# Duckietown_2018C.net
KiCad netlist of a schematic drawn in EAGLE
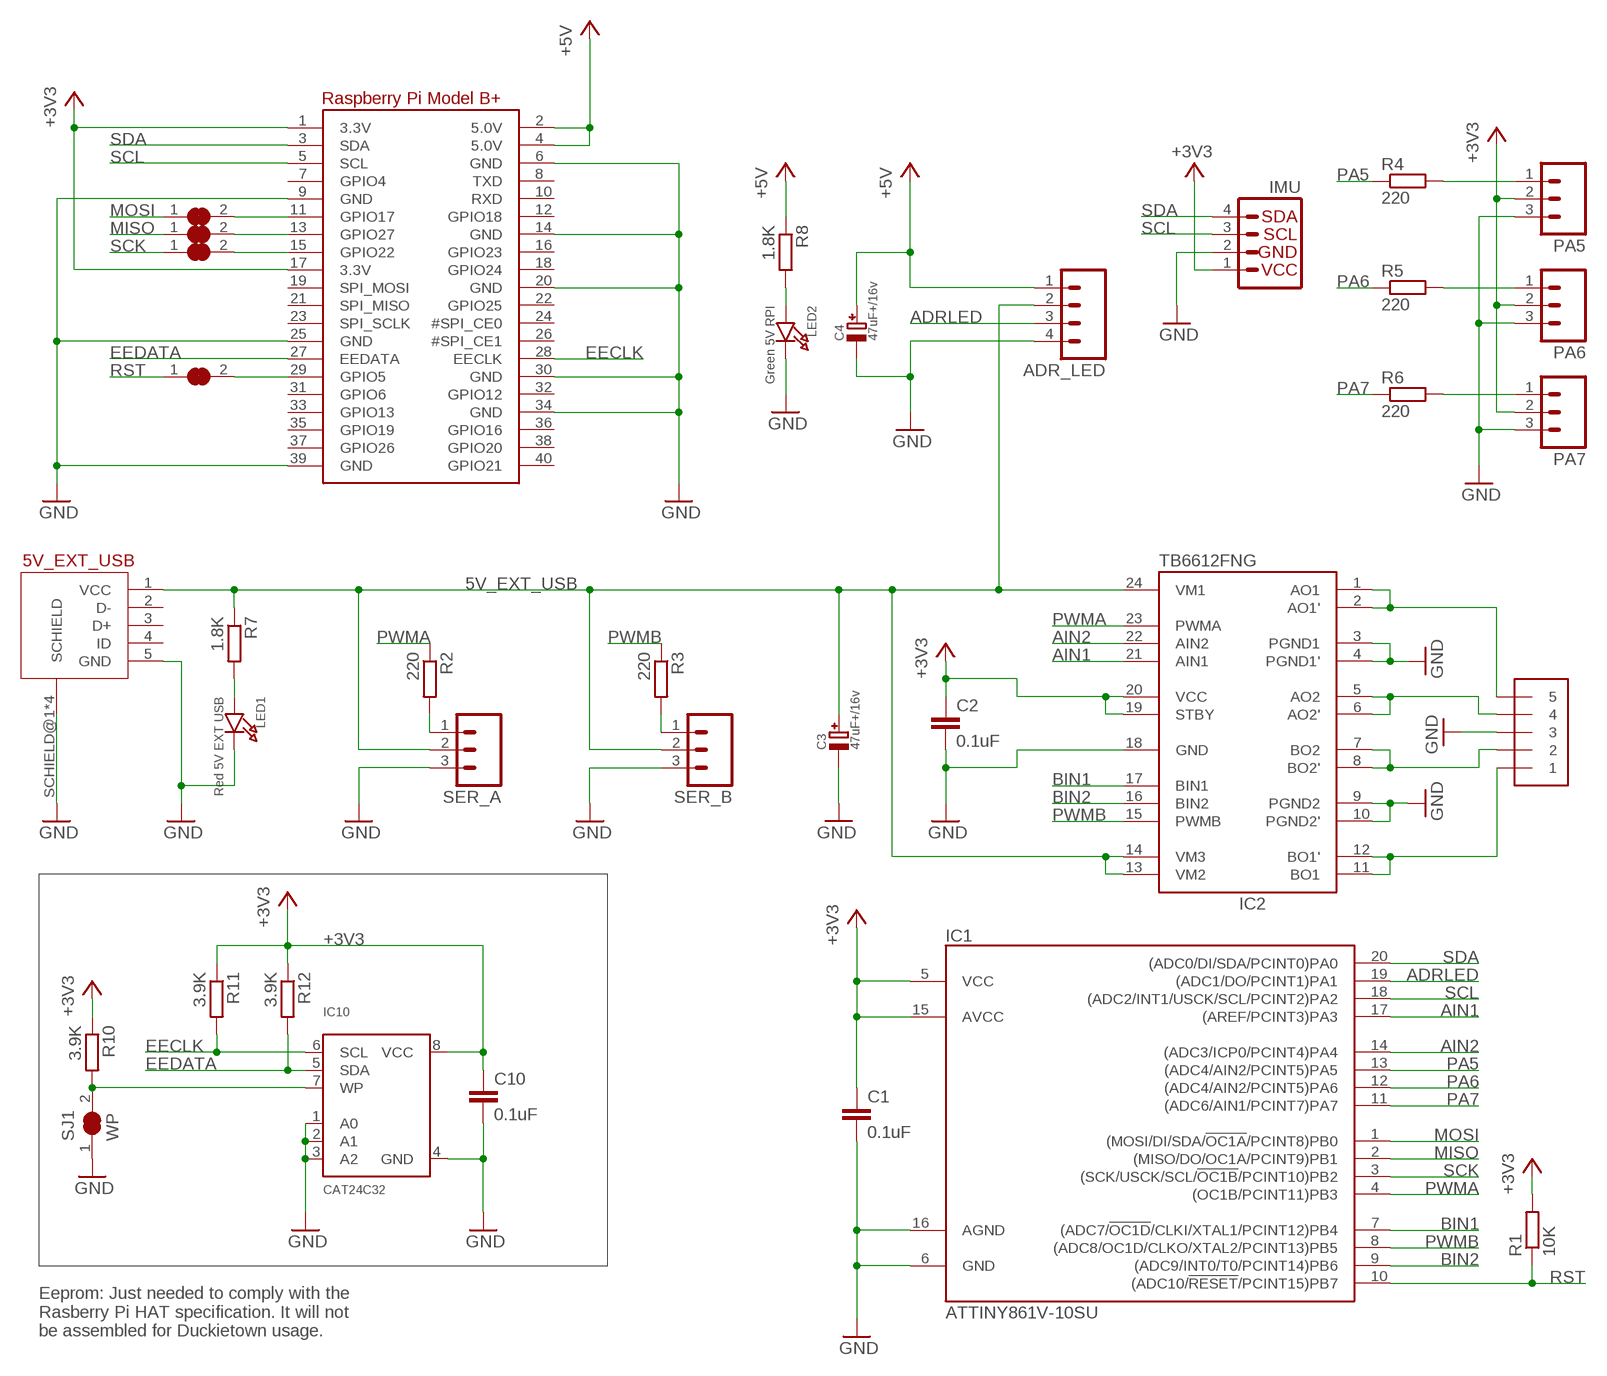
[diagram p0: schematic, sheet 1]

(export (version "E")
  (design (tool "Eeschema 10.0.6"))
  (components
    (comp (ref "5V_EXT_USB")
      (value "MICROUSBCON")
      (footprint "eagle-import:MICROUSBCON")
      (libsource (lib "eagle-import") (part "MICROUSBCON"))
    )
    (comp (ref "ADR_LED")
      (value "M04PTH")
      (footprint "eagle-import:1X04")
      (libsource (lib "eagle-import") (part "M04PTH"))
    )
    (comp (ref "C1")
      (value "0.1uF")
      (footprint "eagle-import:C0603")
      (libsource (lib "eagle-import") (part "C-EUC0603"))
    )
    (comp (ref "C2")
      (value "0.1uF")
      (footprint "eagle-import:C0603")
      (libsource (lib "eagle-import") (part "C-EUC0603"))
    )
    (comp (ref "C3")
      (value "47uF+/16v")
      (footprint "eagle-import:PANASONIC_C")
      (libsource (lib "eagle-import") (part "CAP_ELECTROLYTICPANASONIC_C"))
    )
    (comp (ref "C4")
      (value "47uF+/16v")
      (footprint "eagle-import:PANASONIC_C")
      (libsource (lib "eagle-import") (part "CAP_ELECTROLYTICPANASONIC_C"))
    )
    (comp (ref "C10")
      (value "0.1uF")
      (footprint "eagle-import:C0603")
      (libsource (lib "eagle-import") (part "C-EUC0603"))
    )
    (comp (ref "IC1")
      (value "ATTINY861V-10SU")
      (footprint "eagle-import:SO20L")
      (libsource (lib "eagle-import") (part "ATTINY861V-10SU"))
    )
    (comp (ref "IC2")
      (value "TB6612FNG")
      (footprint "eagle-import:SSOP24")
      (libsource (lib "eagle-import") (part "TB6612FNG"))
    )
    (comp (ref "IC10")
      (value "CAT24C32")
      (footprint "eagle-import:SOIC8_150MIL")
      (libsource (lib "eagle-import") (part "EEPROM_I2C_SOIC8_GENERIC"))
    )
    (comp (ref "IMU")
      (value "I2C_IMU_L3GD20H+LSM303")
      (footprint "eagle-import:1X04")
      (libsource (lib "eagle-import") (part "I2C_IMU_L3GD20H+LSM303"))
    )
    (comp (ref "LED1")
      (value "Red 5V EXT USB")
      (footprint "eagle-import:CHIPLED_0805_NOOUTLINE")
      (libsource (lib "eagle-import") (part "LED0805_NOOUTLINE"))
    )
    (comp (ref "LED2")
      (value "Green 5V RPI")
      (footprint "eagle-import:CHIPLED_0805_NOOUTLINE")
      (libsource (lib "eagle-import") (part "LED0805_NOOUTLINE"))
    )
    (comp (ref "MOTA")
      (value "1X5")
      (footprint "eagle-import:1X05-3.5MM")
      (libsource (lib "eagle-import") (part "1X5"))
    )
    (comp (ref "PA5")
      (value "M03PTH")
      (footprint "eagle-import:1X03")
      (libsource (lib "eagle-import") (part "M03PTH"))
    )
    (comp (ref "PA6")
      (value "M03PTH")
      (footprint "eagle-import:1X03")
      (libsource (lib "eagle-import") (part "M03PTH"))
    )
    (comp (ref "PA7")
      (value "M03PTH")
      (footprint "eagle-import:1X03")
      (libsource (lib "eagle-import") (part "M03PTH"))
    )
    (comp (ref "R1")
      (value "10K")
      (footprint "eagle-import:R0603")
      (libsource (lib "eagle-import") (part "R-EU_R0603"))
    )
    (comp (ref "R2")
      (value "220")
      (footprint "eagle-import:R0603")
      (libsource (lib "eagle-import") (part "R-EU_R0603"))
    )
    (comp (ref "R3")
      (value "220")
      (footprint "eagle-import:R0603")
      (libsource (lib "eagle-import") (part "R-EU_R0603"))
    )
    (comp (ref "R4")
      (value "220")
      (footprint "eagle-import:R0603")
      (libsource (lib "eagle-import") (part "R-EU_R0603"))
    )
    (comp (ref "R5")
      (value "220")
      (footprint "eagle-import:R0603")
      (libsource (lib "eagle-import") (part "R-EU_R0603"))
    )
    (comp (ref "R6")
      (value "220")
      (footprint "eagle-import:R0603")
      (libsource (lib "eagle-import") (part "R-EU_R0603"))
    )
    (comp (ref "R7")
      (value "1.8K")
      (footprint "eagle-import:R0603")
      (libsource (lib "eagle-import") (part "R-EU_R0603"))
    )
    (comp (ref "R8")
      (value "1.8K")
      (footprint "eagle-import:R0603")
      (libsource (lib "eagle-import") (part "R-EU_R0603"))
    )
    (comp (ref "R10")
      (value "3.9K")
      (footprint "eagle-import:R0603")
      (libsource (lib "eagle-import") (part "R-EU_R0603"))
    )
    (comp (ref "R11")
      (value "3.9K")
      (footprint "eagle-import:R0603")
      (libsource (lib "eagle-import") (part "R-EU_R0603"))
    )
    (comp (ref "R12")
      (value "3.9K")
      (footprint "eagle-import:R0603")
      (libsource (lib "eagle-import") (part "R-EU_R0603"))
    )
    (comp (ref "RPI2")
      (value "RASPBERRYPI_BPLUS_HATSLOTS")
      (footprint "eagle-import:PI_HAT_SLOTS")
      (libsource (lib "eagle-import") (part "RASPBERRYPI_BPLUS_HATSLOTS"))
    )
    (comp (ref "RP_MISO")
      (value "SOLDERJUMPER_CLOSED")
      (footprint "eagle-import:SOLDERJUMPER_CLOSEDWIRE")
      (libsource (lib "eagle-import") (part "SOLDERJUMPER_CLOSED"))
    )
    (comp (ref "RP_MOSI")
      (value "SOLDERJUMPER_CLOSED")
      (footprint "eagle-import:SOLDERJUMPER_CLOSEDWIRE")
      (libsource (lib "eagle-import") (part "SOLDERJUMPER_CLOSED"))
    )
    (comp (ref "RP_RST")
      (value "SOLDERJUMPER_CLOSED")
      (footprint "eagle-import:SOLDERJUMPER_CLOSEDWIRE")
      (libsource (lib "eagle-import") (part "SOLDERJUMPER_CLOSED"))
    )
    (comp (ref "RP_SCK")
      (value "SOLDERJUMPER_CLOSED")
      (footprint "eagle-import:SOLDERJUMPER_CLOSEDWIRE")
      (libsource (lib "eagle-import") (part "SOLDERJUMPER_CLOSED"))
    )
    (comp (ref "SER_A")
      (value "M03PTH")
      (footprint "eagle-import:1X03")
      (libsource (lib "eagle-import") (part "M03PTH"))
    )
    (comp (ref "SER_B")
      (value "M03PTH")
      (footprint "eagle-import:1X03")
      (libsource (lib "eagle-import") (part "M03PTH"))
    )
    (comp (ref "SJ1")
      (value "WP")
      (footprint "eagle-import:SOLDERJUMPER_CLOSEDWIRE")
      (libsource (lib "eagle-import") (part "SOLDERJUMPER_CLOSED"))
    )
  )
  (nets
    (net (code "1") (name "+3V3") (class "Default")
      (node (ref "C1") (pin "1") (pinfunction "1_1") (pintype "passive"))
      (node (ref "C10") (pin "1") (pinfunction "1_1") (pintype "passive"))
      (node (ref "C2") (pin "1") (pinfunction "1_1") (pintype "passive"))
      (node (ref "IC1") (pin "15") (pinfunction "AVCC_15") (pintype "power_in"))
      (node (ref "IC1") (pin "5") (pinfunction "VCC_5") (pintype "power_in"))
      (node (ref "IC10") (pin "8") (pinfunction "VCC_8") (pintype "power_in"))
      (node (ref "IC2") (pin "19") (pinfunction "STBY_19") (pintype "input"))
      (node (ref "IC2") (pin "20") (pinfunction "VCC_20") (pintype "power_in"))
      (node (ref "IMU") (pin "1") (pinfunction "1_1") (pintype "passive"))
      (node (ref "PA5") (pin "2") (pinfunction "2_2") (pintype "passive"))
      (node (ref "PA6") (pin "2") (pinfunction "2_2") (pintype "passive"))
      (node (ref "PA7") (pin "2") (pinfunction "2_2") (pintype "passive"))
      (node (ref "R1") (pin "2") (pinfunction "2_2") (pintype "passive"))
      (node (ref "R10") (pin "1") (pinfunction "1_1") (pintype "passive"))
      (node (ref "R11") (pin "1") (pinfunction "1_1") (pintype "passive"))
      (node (ref "R12") (pin "1") (pinfunction "1_1") (pintype "passive"))
      (node (ref "RPI2") (pin "1") (pinfunction "3.3V_1") (pintype "power_in"))
      (node (ref "RPI2") (pin "17") (pinfunction "3.3V_17") (pintype "power_in"))
    )
    (net (code "2") (name "+5V") (class "Default")
      (node (ref "ADR_LED") (pin "1") (pinfunction "1_1") (pintype "passive"))
      (node (ref "C4") (pin "+") (pinfunction "+_+") (pintype "passive"))
      (node (ref "R8") (pin "1") (pinfunction "1_1") (pintype "passive"))
      (node (ref "RPI2") (pin "2") (pinfunction "5.0V_2") (pintype "power_in"))
      (node (ref "RPI2") (pin "4") (pinfunction "5.0V_4") (pintype "power_in"))
    )
    (net (code "3") (name "/5V_EXT_USB") (class "Default")
      (node (ref "5V_EXT_USB") (pin "1") (pinfunction "VCC_1") (pintype "power_in"))
      (node (ref "ADR_LED") (pin "2") (pinfunction "2_2") (pintype "passive"))
      (node (ref "C3") (pin "+") (pinfunction "+_+") (pintype "passive"))
      (node (ref "IC2") (pin "13") (pinfunction "VM2_13") (pintype "power_in"))
      (node (ref "IC2") (pin "14") (pinfunction "VM3_14") (pintype "power_in"))
      (node (ref "IC2") (pin "24") (pinfunction "VM1_24") (pintype "power_in"))
      (node (ref "R7") (pin "1") (pinfunction "1_1") (pintype "passive"))
      (node (ref "SER_A") (pin "2") (pinfunction "2_2") (pintype "passive"))
      (node (ref "SER_B") (pin "2") (pinfunction "2_2") (pintype "passive"))
    )
    (net (code "4") (name "/ADRLED") (class "Default")
      (node (ref "ADR_LED") (pin "3") (pinfunction "3_3") (pintype "passive"))
      (node (ref "IC1") (pin "19") (pinfunction "(ADC1/DO/PCINT1)PA1_19") (pintype "bidirectional"))
    )
    (net (code "5") (name "/AIN1") (class "Default")
      (node (ref "IC1") (pin "17") (pinfunction "(AREF/PCINT3)PA3_17") (pintype "bidirectional"))
      (node (ref "IC2") (pin "21") (pinfunction "AIN1_21") (pintype "input"))
    )
    (net (code "6") (name "/AIN2") (class "Default")
      (node (ref "IC1") (pin "14") (pinfunction "(ADC3/ICP0/PCINT4)PA4_14") (pintype "bidirectional"))
      (node (ref "IC2") (pin "22") (pinfunction "AIN2_22") (pintype "input"))
    )
    (net (code "7") (name "/BIN1") (class "Default")
      (node (ref "IC1") (pin "7") (pinfunction "(ADC7/~{OC1D}/CLKI/XTAL1/PCINT12)PB4_7") (pintype "bidirectional"))
      (node (ref "IC2") (pin "17") (pinfunction "BIN1_17") (pintype "input"))
    )
    (net (code "8") (name "/BIN2") (class "Default")
      (node (ref "IC1") (pin "9") (pinfunction "(ADC9/INT0/T0/PCINT14)PB6_9") (pintype "bidirectional"))
      (node (ref "IC2") (pin "16") (pinfunction "BIN2_16") (pintype "input"))
    )
    (net (code "9") (name "/EECLK") (class "Default")
      (node (ref "IC10") (pin "6") (pinfunction "SCL_6") (pintype "input"))
      (node (ref "R11") (pin "2") (pinfunction "2_2") (pintype "passive"))
      (node (ref "RPI2") (pin "28") (pinfunction "EECLK_28") (pintype "power_in"))
    )
    (net (code "10") (name "/EEDATA") (class "Default")
      (node (ref "IC10") (pin "5") (pinfunction "SDA_5") (pintype "bidirectional"))
      (node (ref "R12") (pin "2") (pinfunction "2_2") (pintype "passive"))
      (node (ref "RPI2") (pin "27") (pinfunction "EEDATA_27") (pintype "bidirectional"))
    )
    (net (code "11") (name "/GPIO6") (class "Default")
      (node (ref "RPI2") (pin "31") (pinfunction "GPIO6_31") (pintype "power_in"))
    )
    (net (code "12") (name "/GPIO16") (class "Default")
      (node (ref "RPI2") (pin "36") (pinfunction "GPIO16_36") (pintype "power_in"))
    )
    (net (code "13") (name "/MISO") (class "Default")
      (node (ref "IC1") (pin "2") (pinfunction "(MISO/DO/OC1A/PCINT9)PB1_2") (pintype "bidirectional"))
      (node (ref "RP_MISO") (pin "1") (pinfunction "1_1") (pintype "passive"))
    )
    (net (code "14") (name "/MOSI") (class "Default")
      (node (ref "IC1") (pin "1") (pinfunction "(MOSI/DI/SDA/~{OC1A}/PCINT8)PB0_1") (pintype "bidirectional"))
      (node (ref "RP_MOSI") (pin "1") (pinfunction "1_1") (pintype "passive"))
    )
    (net (code "15") (name "/PA5") (class "Default")
      (node (ref "IC1") (pin "13") (pinfunction "(ADC4/AIN2/PCINT5)PA5_13") (pintype "bidirectional"))
      (node (ref "R4") (pin "1") (pinfunction "1_1") (pintype "passive"))
    )
    (net (code "16") (name "/PA6") (class "Default")
      (node (ref "IC1") (pin "12") (pinfunction "(ADC4/AIN2/PCINT5)PA6_12") (pintype "bidirectional"))
      (node (ref "R5") (pin "1") (pinfunction "1_1") (pintype "passive"))
    )
    (net (code "17") (name "/PA7") (class "Default")
      (node (ref "IC1") (pin "11") (pinfunction "(ADC6/AIN1/PCINT7)PA7_11") (pintype "bidirectional"))
      (node (ref "R6") (pin "1") (pinfunction "1_1") (pintype "passive"))
    )
    (net (code "18") (name "/PWMA") (class "Default")
      (node (ref "IC1") (pin "4") (pinfunction "(OC1B/PCINT11)PB3_4") (pintype "bidirectional"))
      (node (ref "IC2") (pin "23") (pinfunction "PWMA_23") (pintype "input"))
      (node (ref "R2") (pin "1") (pinfunction "1_1") (pintype "passive"))
    )
    (net (code "19") (name "/PWMB") (class "Default")
      (node (ref "IC1") (pin "8") (pinfunction "(ADC8/OC1D/CLKO/XTAL2/PCINT13)PB5_8") (pintype "bidirectional"))
      (node (ref "IC2") (pin "15") (pinfunction "PWMB_15") (pintype "input"))
      (node (ref "R3") (pin "1") (pinfunction "1_1") (pintype "passive"))
    )
    (net (code "20") (name "/RST") (class "Default")
      (node (ref "IC1") (pin "10") (pinfunction "(ADC10/~{RESET}/PCINT15)PB7_10") (pintype "bidirectional"))
      (node (ref "R1") (pin "1") (pinfunction "1_1") (pintype "passive"))
      (node (ref "RP_RST") (pin "1") (pinfunction "1_1") (pintype "passive"))
    )
    (net (code "21") (name "/SCK") (class "Default")
      (node (ref "IC1") (pin "3") (pinfunction "(SCK/USCK/SCL/~{OC1B}/PCINT10)PB2_3") (pintype "bidirectional"))
      (node (ref "RP_SCK") (pin "1") (pinfunction "1_1") (pintype "passive"))
    )
    (net (code "22") (name "/SCL") (class "Default")
      (node (ref "IC1") (pin "18") (pinfunction "(ADC2/INT1/USCK/SCL/PCINT2)PA2_18") (pintype "bidirectional"))
      (node (ref "IMU") (pin "3") (pinfunction "3_3") (pintype "passive"))
      (node (ref "RPI2") (pin "5") (pinfunction "SCL_5") (pintype "bidirectional"))
    )
    (net (code "23") (name "/SDA") (class "Default")
      (node (ref "IC1") (pin "20") (pinfunction "(ADC0/DI/SDA/PCINT0)PA0_20") (pintype "bidirectional"))
      (node (ref "IMU") (pin "4") (pinfunction "4_4") (pintype "passive"))
      (node (ref "RPI2") (pin "3") (pinfunction "SDA_3") (pintype "bidirectional"))
    )
    (net (code "24") (name "GND") (class "Default")
      (node (ref "5V_EXT_USB") (pin "5") (pinfunction "GND_5") (pintype "power_in"))
      (node (ref "5V_EXT_USB") (pin "SCHIELD@1") (pinfunction "SCHIELD_SCHIELD@1") (pintype "bidirectional"))
      (node (ref "5V_EXT_USB") (pin "SCHIELD@2") (pinfunction "SCHIELD_SCHIELD@2") (pintype "bidirectional"))
      (node (ref "5V_EXT_USB") (pin "SCHIELD@3") (pinfunction "SCHIELD_SCHIELD@3") (pintype "bidirectional"))
      (node (ref "5V_EXT_USB") (pin "SCHIELD@4") (pinfunction "SCHIELD_SCHIELD@4") (pintype "bidirectional"))
      (node (ref "ADR_LED") (pin "4") (pinfunction "4_4") (pintype "passive"))
      (node (ref "C1") (pin "2") (pinfunction "2_2") (pintype "passive"))
      (node (ref "C10") (pin "2") (pinfunction "2_2") (pintype "passive"))
      (node (ref "C2") (pin "2") (pinfunction "2_2") (pintype "passive"))
      (node (ref "C3") (pin "-") (pinfunction "-_-") (pintype "passive"))
      (node (ref "C4") (pin "-") (pinfunction "-_-") (pintype "passive"))
      (node (ref "IC1") (pin "16") (pinfunction "AGND_16") (pintype "power_in"))
      (node (ref "IC1") (pin "6") (pinfunction "GND_6") (pintype "power_in"))
      (node (ref "IC10") (pin "1") (pinfunction "A0_1") (pintype "input"))
      (node (ref "IC10") (pin "2") (pinfunction "A1_2") (pintype "input"))
      (node (ref "IC10") (pin "3") (pinfunction "A2_3") (pintype "input"))
      (node (ref "IC10") (pin "4") (pinfunction "GND_4") (pintype "power_in"))
      (node (ref "IC2") (pin "10") (pinfunction "PGND2'_10") (pintype "power_in"))
      (node (ref "IC2") (pin "18") (pinfunction "GND_18") (pintype "power_in"))
      (node (ref "IC2") (pin "3") (pinfunction "PGND1_3") (pintype "power_in"))
      (node (ref "IC2") (pin "4") (pinfunction "PGND1'_4") (pintype "power_in"))
      (node (ref "IC2") (pin "9") (pinfunction "PGND2_9") (pintype "power_in"))
      (node (ref "IMU") (pin "2") (pinfunction "2_2") (pintype "passive"))
      (node (ref "LED1") (pin "C") (pinfunction "C_C") (pintype "passive"))
      (node (ref "LED2") (pin "C") (pinfunction "C_C") (pintype "passive"))
      (node (ref "MOTA") (pin "3") (pinfunction "3_3") (pintype "passive"))
      (node (ref "PA5") (pin "3") (pinfunction "3_3") (pintype "passive"))
      (node (ref "PA6") (pin "3") (pinfunction "3_3") (pintype "passive"))
      (node (ref "PA7") (pin "3") (pinfunction "3_3") (pintype "passive"))
      (node (ref "RPI2") (pin "14") (pinfunction "GND_14") (pintype "power_in"))
      (node (ref "RPI2") (pin "20") (pinfunction "GND_20") (pintype "power_in"))
      (node (ref "RPI2") (pin "25") (pinfunction "GND_25") (pintype "power_in"))
      (node (ref "RPI2") (pin "30") (pinfunction "GND_30") (pintype "bidirectional"))
      (node (ref "RPI2") (pin "34") (pinfunction "GND_34") (pintype "bidirectional"))
      (node (ref "RPI2") (pin "39") (pinfunction "GND_39") (pintype "power_in"))
      (node (ref "RPI2") (pin "6") (pinfunction "GND_6") (pintype "power_in"))
      (node (ref "RPI2") (pin "9") (pinfunction "GND_9") (pintype "power_in"))
      (node (ref "SER_A") (pin "3") (pinfunction "3_3") (pintype "passive"))
      (node (ref "SER_B") (pin "3") (pinfunction "3_3") (pintype "passive"))
      (node (ref "SJ1") (pin "1") (pinfunction "1_1") (pintype "passive"))
    )
    (net (code "25") (name "Net-(IC2-AO1')") (class "Default")
      (node (ref "IC2") (pin "1") (pinfunction "AO1_1") (pintype "output"))
      (node (ref "IC2") (pin "2") (pinfunction "AO1'_2") (pintype "output"))
      (node (ref "MOTA") (pin "5") (pinfunction "5_5") (pintype "passive"))
    )
    (net (code "26") (name "Net-(IC2-AO2')") (class "Default")
      (node (ref "IC2") (pin "5") (pinfunction "AO2_5") (pintype "output"))
      (node (ref "IC2") (pin "6") (pinfunction "AO2'_6") (pintype "output"))
      (node (ref "MOTA") (pin "4") (pinfunction "4_4") (pintype "passive"))
    )
    (net (code "27") (name "Net-(IC2-BO1')") (class "Default")
      (node (ref "IC2") (pin "11") (pinfunction "BO1_11") (pintype "output"))
      (node (ref "IC2") (pin "12") (pinfunction "BO1'_12") (pintype "output"))
      (node (ref "MOTA") (pin "1") (pinfunction "1_1") (pintype "passive"))
    )
    (net (code "28") (name "Net-(IC2-BO2')") (class "Default")
      (node (ref "IC2") (pin "7") (pinfunction "BO2_7") (pintype "output"))
      (node (ref "IC2") (pin "8") (pinfunction "BO2'_8") (pintype "output"))
      (node (ref "MOTA") (pin "2") (pinfunction "2_2") (pintype "passive"))
    )
    (net (code "29") (name "Net-(IC10-WP)") (class "Default")
      (node (ref "IC10") (pin "7") (pinfunction "WP_7") (pintype "input"))
      (node (ref "R10") (pin "2") (pinfunction "2_2") (pintype "passive"))
      (node (ref "SJ1") (pin "2") (pinfunction "2_2") (pintype "passive"))
    )
    (net (code "30") (name "Net-(LED1-PadA)") (class "Default")
      (node (ref "LED1") (pin "A") (pinfunction "A_A") (pintype "passive"))
      (node (ref "R7") (pin "2") (pinfunction "2_2") (pintype "passive"))
    )
    (net (code "31") (name "Net-(LED2-PadA)") (class "Default")
      (node (ref "LED2") (pin "A") (pinfunction "A_A") (pintype "passive"))
      (node (ref "R8") (pin "2") (pinfunction "2_2") (pintype "passive"))
    )
    (net (code "32") (name "Net-(PA5-Pad1)") (class "Default")
      (node (ref "PA5") (pin "1") (pinfunction "1_1") (pintype "passive"))
      (node (ref "R4") (pin "2") (pinfunction "2_2") (pintype "passive"))
    )
    (net (code "33") (name "Net-(PA6-Pad1)") (class "Default")
      (node (ref "PA6") (pin "1") (pinfunction "1_1") (pintype "passive"))
      (node (ref "R5") (pin "2") (pinfunction "2_2") (pintype "passive"))
    )
    (net (code "34") (name "Net-(PA7-Pad1)") (class "Default")
      (node (ref "PA7") (pin "1") (pinfunction "1_1") (pintype "passive"))
      (node (ref "R6") (pin "2") (pinfunction "2_2") (pintype "passive"))
    )
    (net (code "35") (name "Net-(R2-Pad2)") (class "Default")
      (node (ref "R2") (pin "2") (pinfunction "2_2") (pintype "passive"))
      (node (ref "SER_A") (pin "1") (pinfunction "1_1") (pintype "passive"))
    )
    (net (code "36") (name "Net-(R3-Pad2)") (class "Default")
      (node (ref "R3") (pin "2") (pinfunction "2_2") (pintype "passive"))
      (node (ref "SER_B") (pin "1") (pinfunction "1_1") (pintype "passive"))
    )
    (net (code "37") (name "Net-(RPI2-GPIO5)") (class "Default")
      (node (ref "RPI2") (pin "29") (pinfunction "GPIO5_29") (pintype "bidirectional"))
      (node (ref "RP_RST") (pin "2") (pinfunction "2_2") (pintype "passive"))
    )
    (net (code "38") (name "Net-(RPI2-GPIO17)") (class "Default")
      (node (ref "RPI2") (pin "11") (pinfunction "GPIO17_11") (pintype "bidirectional"))
      (node (ref "RP_MOSI") (pin "2") (pinfunction "2_2") (pintype "passive"))
    )
    (net (code "39") (name "Net-(RPI2-GPIO22)") (class "Default")
      (node (ref "RPI2") (pin "15") (pinfunction "GPIO22_15") (pintype "bidirectional"))
      (node (ref "RP_SCK") (pin "2") (pinfunction "2_2") (pintype "passive"))
    )
    (net (code "40") (name "Net-(RPI2-GPIO27)") (class "Default")
      (node (ref "RPI2") (pin "13") (pinfunction "GPIO27_13") (pintype "bidirectional"))
      (node (ref "RP_MISO") (pin "2") (pinfunction "2_2") (pintype "passive"))
    )
    (net (code "41") (name "unconnected-(5V_EXT_USB-D+-Pad3)") (class "Default")
      (node (ref "5V_EXT_USB") (pin "3") (pinfunction "D+_3") (pintype "bidirectional"))
    )
    (net (code "42") (name "unconnected-(5V_EXT_USB-D--Pad2)") (class "Default")
      (node (ref "5V_EXT_USB") (pin "2") (pinfunction "D-_2") (pintype "bidirectional"))
    )
    (net (code "43") (name "unconnected-(5V_EXT_USB-ID-Pad4)") (class "Default")
      (node (ref "5V_EXT_USB") (pin "4") (pinfunction "ID_4") (pintype "bidirectional"))
    )
    (net (code "44") (name "unconnected-(RPI2-#SPI_CE0-Pad24)") (class "Default")
      (node (ref "RPI2") (pin "24") (pinfunction "#SPI_CE0_24") (pintype "bidirectional"))
    )
    (net (code "45") (name "unconnected-(RPI2-#SPI_CE1-Pad26)") (class "Default")
      (node (ref "RPI2") (pin "26") (pinfunction "#SPI_CE1_26") (pintype "bidirectional"))
    )
    (net (code "46") (name "unconnected-(RPI2-GPIO4-Pad7)") (class "Default")
      (node (ref "RPI2") (pin "7") (pinfunction "GPIO4_7") (pintype "bidirectional"))
    )
    (net (code "47") (name "unconnected-(RPI2-GPIO12-Pad32)") (class "Default")
      (node (ref "RPI2") (pin "32") (pinfunction "GPIO12_32") (pintype "bidirectional"))
    )
    (net (code "48") (name "unconnected-(RPI2-GPIO13-Pad33)") (class "Default")
      (node (ref "RPI2") (pin "33") (pinfunction "GPIO13_33") (pintype "bidirectional"))
    )
    (net (code "49") (name "unconnected-(RPI2-GPIO18-Pad12)") (class "Default")
      (node (ref "RPI2") (pin "12") (pinfunction "GPIO18_12") (pintype "bidirectional"))
    )
    (net (code "50") (name "unconnected-(RPI2-GPIO19-Pad35)") (class "Default")
      (node (ref "RPI2") (pin "35") (pinfunction "GPIO19_35") (pintype "bidirectional"))
    )
    (net (code "51") (name "unconnected-(RPI2-GPIO20-Pad38)") (class "Default")
      (node (ref "RPI2") (pin "38") (pinfunction "GPIO20_38") (pintype "bidirectional"))
    )
    (net (code "52") (name "unconnected-(RPI2-GPIO21-Pad40)") (class "Default")
      (node (ref "RPI2") (pin "40") (pinfunction "GPIO21_40") (pintype "bidirectional"))
    )
    (net (code "53") (name "unconnected-(RPI2-GPIO23-Pad16)") (class "Default")
      (node (ref "RPI2") (pin "16") (pinfunction "GPIO23_16") (pintype "bidirectional"))
    )
    (net (code "54") (name "unconnected-(RPI2-GPIO24-Pad18)") (class "Default")
      (node (ref "RPI2") (pin "18") (pinfunction "GPIO24_18") (pintype "bidirectional"))
    )
    (net (code "55") (name "unconnected-(RPI2-GPIO25-Pad22)") (class "Default")
      (node (ref "RPI2") (pin "22") (pinfunction "GPIO25_22") (pintype "bidirectional"))
    )
    (net (code "56") (name "unconnected-(RPI2-GPIO26-Pad37)") (class "Default")
      (node (ref "RPI2") (pin "37") (pinfunction "GPIO26_37") (pintype "bidirectional"))
    )
    (net (code "57") (name "unconnected-(RPI2-RXD-Pad10)") (class "Default")
      (node (ref "RPI2") (pin "10") (pinfunction "RXD_10") (pintype "bidirectional"))
    )
    (net (code "58") (name "unconnected-(RPI2-SPI_MISO-Pad21)") (class "Default")
      (node (ref "RPI2") (pin "21") (pinfunction "SPI_MISO_21") (pintype "bidirectional"))
    )
    (net (code "59") (name "unconnected-(RPI2-SPI_MOSI-Pad19)") (class "Default")
      (node (ref "RPI2") (pin "19") (pinfunction "SPI_MOSI_19") (pintype "bidirectional"))
    )
    (net (code "60") (name "unconnected-(RPI2-SPI_SCLK-Pad23)") (class "Default")
      (node (ref "RPI2") (pin "23") (pinfunction "SPI_SCLK_23") (pintype "bidirectional"))
    )
    (net (code "61") (name "unconnected-(RPI2-TXD-Pad8)") (class "Default")
      (node (ref "RPI2") (pin "8") (pinfunction "TXD_8") (pintype "output"))
    )
  )
)
